# 01_FETCH_INCREMENT.net
KiCad netlist of a schematic drawn in EAGLE
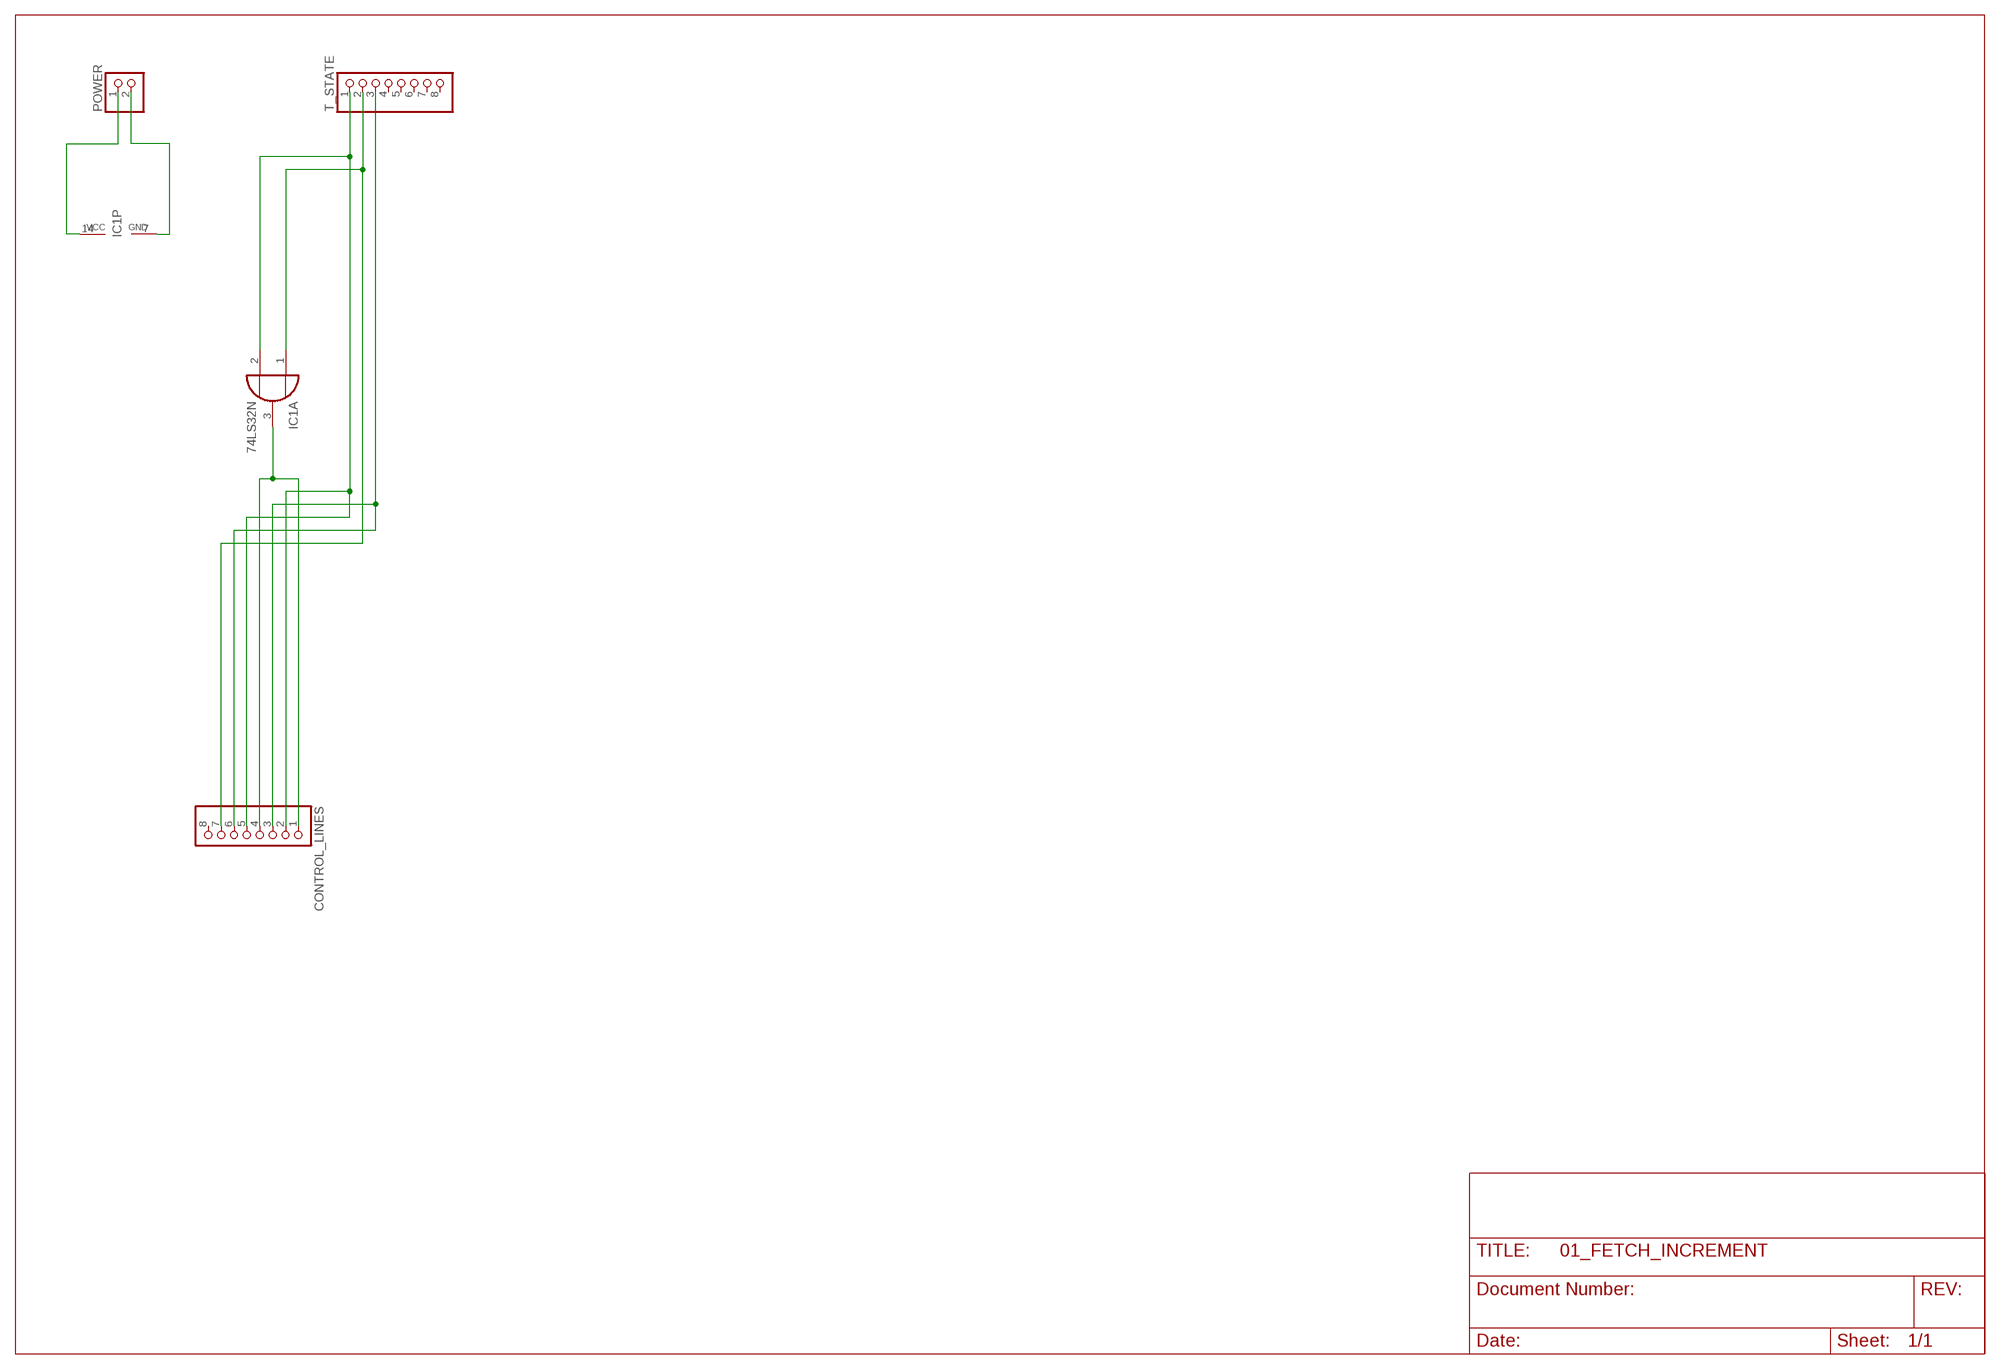
[diagram p0: schematic, sheet 1]

(export (version "E")
  (design (tool "Eeschema 10.0.6"))
  (components
    (comp (ref "CONTROL_LINES")
      (value "PINHD-1X8")
      (footprint "eagle-import:1X08")
      (libsource (lib "eagle-import") (part "PINHD-1X8"))
    )
    (comp (ref "IC1")
      (value "74LS32N")
      (footprint "eagle-import:DIL14")
      (libsource (lib "eagle-import") (part "7432NLS"))
    )
    (comp (ref "POWER")
      (value "PINHD-1X2")
      (footprint "eagle-import:1X02")
      (libsource (lib "eagle-import") (part "PINHD-1X2"))
    )
    (comp (ref "T_STATE")
      (value "PINHD-1X8")
      (footprint "eagle-import:1X08")
      (libsource (lib "eagle-import") (part "PINHD-1X8"))
    )
  )
  (nets
    (net (code "1") (name "Net-(CONTROL_LINES-Pad3)") (class "Default")
      (node (ref "CONTROL_LINES") (pin "3") (pinfunction "3_3") (pintype "passive"))
      (node (ref "CONTROL_LINES") (pin "6") (pinfunction "6_6") (pintype "passive"))
      (node (ref "T_STATE") (pin "3") (pinfunction "3_3") (pintype "passive"))
    )
    (net (code "2") (name "Net-(IC1A-I0)") (class "Default")
      (node (ref "CONTROL_LINES") (pin "7") (pinfunction "7_7") (pintype "passive"))
      (node (ref "IC1") (pin "1") (pinfunction "I0_1") (pintype "input"))
      (node (ref "T_STATE") (pin "2") (pinfunction "2_2") (pintype "passive"))
    )
    (net (code "3") (name "Net-(IC1A-I1)") (class "Default")
      (node (ref "CONTROL_LINES") (pin "2") (pinfunction "2_2") (pintype "passive"))
      (node (ref "CONTROL_LINES") (pin "5") (pinfunction "5_5") (pintype "passive"))
      (node (ref "IC1") (pin "2") (pinfunction "I1_2") (pintype "input"))
      (node (ref "T_STATE") (pin "1") (pinfunction "1_1") (pintype "passive"))
    )
    (net (code "4") (name "Net-(IC1A-O)") (class "Default")
      (node (ref "CONTROL_LINES") (pin "1") (pinfunction "1_1") (pintype "passive"))
      (node (ref "CONTROL_LINES") (pin "4") (pinfunction "4_4") (pintype "passive"))
      (node (ref "IC1") (pin "3") (pinfunction "O_3") (pintype "output"))
    )
    (net (code "5") (name "Net-(IC1E-GND)") (class "Default")
      (node (ref "IC1") (pin "7") (pinfunction "GND_7") (pintype "power_in"))
      (node (ref "POWER") (pin "2") (pinfunction "2_2") (pintype "passive"))
    )
    (net (code "6") (name "Net-(IC1E-VCC)") (class "Default")
      (node (ref "IC1") (pin "14") (pinfunction "VCC_14") (pintype "power_in"))
      (node (ref "POWER") (pin "1") (pinfunction "1_1") (pintype "passive"))
    )
    (net (code "7") (name "unconnected-(CONTROL_LINES-Pad8)") (class "Default")
      (node (ref "CONTROL_LINES") (pin "8") (pinfunction "8_8") (pintype "passive"))
    )
    (net (code "8") (name "unconnected-(T_STATE-Pad4)") (class "Default")
      (node (ref "T_STATE") (pin "4") (pinfunction "4_4") (pintype "passive"))
    )
    (net (code "9") (name "unconnected-(T_STATE-Pad5)") (class "Default")
      (node (ref "T_STATE") (pin "5") (pinfunction "5_5") (pintype "passive"))
    )
    (net (code "10") (name "unconnected-(T_STATE-Pad6)") (class "Default")
      (node (ref "T_STATE") (pin "6") (pinfunction "6_6") (pintype "passive"))
    )
    (net (code "11") (name "unconnected-(T_STATE-Pad7)") (class "Default")
      (node (ref "T_STATE") (pin "7") (pinfunction "7_7") (pintype "passive"))
    )
    (net (code "12") (name "unconnected-(T_STATE-Pad8)") (class "Default")
      (node (ref "T_STATE") (pin "8") (pinfunction "8_8") (pintype "passive"))
    )
  )
)
